# untitled.net
KiCad netlist of a schematic drawn in EAGLE
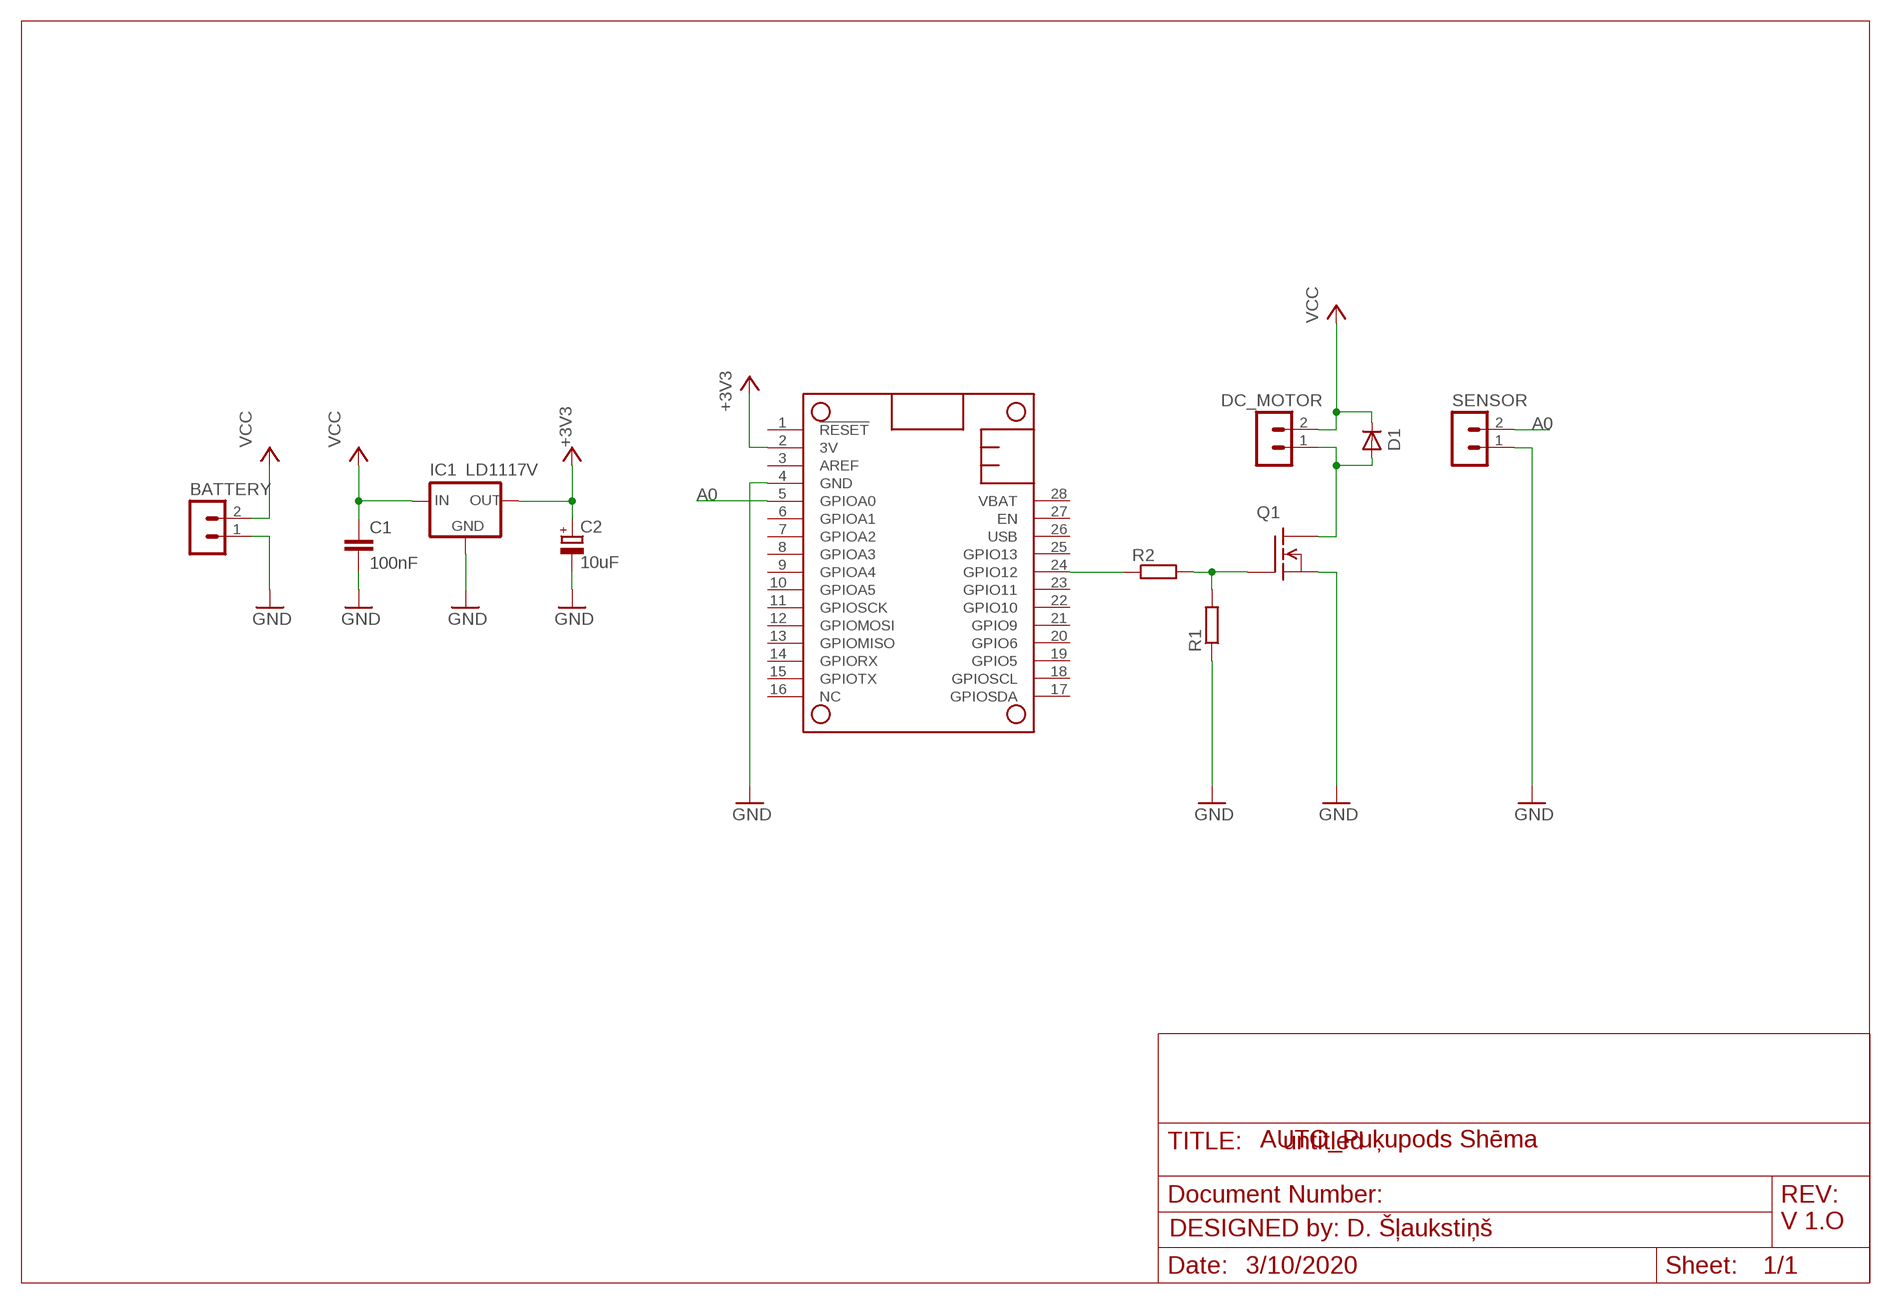
[diagram p0: schematic, sheet 1]

(export (version "E")
  (design (tool "Eeschema 10.0.6"))
  (components
    (comp (ref "BATTERY")
      (value "JST02_2.54")
      (footprint "eagle-import:JST02_2.54")
      (libsource (lib "eagle-import") (part "JST02_2.54"))
    )
    (comp (ref "C1")
      (value "100nF")
      (footprint "eagle-import:SMD_0603C")
      (libsource (lib "eagle-import") (part "CAP_CERAMIC_0603"))
    )
    (comp (ref "C2")
      (value "10uF")
      (footprint "eagle-import:E2,5-5")
      (libsource (lib "eagle-import") (part "CAP_POL_5MM"))
    )
    (comp (ref "D1")
      (value "1N4004")
      (footprint "eagle-import:DO41-10")
      (libsource (lib "eagle-import") (part "1N4004"))
    )
    (comp (ref "DC_MOTOR")
      (value "JST02_2.54")
      (footprint "eagle-import:JST02_2.54")
      (libsource (lib "eagle-import") (part "JST02_2.54"))
    )
    (comp (ref "IC1")
      (value "LD1117V")
      (footprint "eagle-import:78XXL")
      (libsource (lib "eagle-import") (part "V_REG_LD1117VXX"))
    )
    (comp (ref "MS1")
      (value "FEATHERWING")
      (footprint "eagle-import:FEATHERWING")
      (libsource (lib "eagle-import") (part "FEATHERWING"))
    )
    (comp (ref "Q1")
      (value "BSS97")
      (footprint "eagle-import:TO202")
      (libsource (lib "eagle-import") (part "BSS97"))
    )
    (comp (ref "R1")
      (value "RESISTOR_7.5MM_HORIZONTAL")
      (footprint "eagle-import:R-7.5MM")
      (libsource (lib "eagle-import") (part "RESISTOR_7.5MM_HORIZONTAL"))
    )
    (comp (ref "R2")
      (value "RESISTOR_7.5MM_HORIZONTAL")
      (footprint "eagle-import:R-7.5MM")
      (libsource (lib "eagle-import") (part "RESISTOR_7.5MM_HORIZONTAL"))
    )
    (comp (ref "SENSOR")
      (value "JST02_2.54")
      (footprint "eagle-import:JST02_2.54")
      (libsource (lib "eagle-import") (part "JST02_2.54"))
    )
  )
  (nets
    (net (code "1") (name "+3V3") (class "Default")
      (node (ref "C2") (pin "+") (pinfunction "+_+") (pintype "passive"))
      (node (ref "IC1") (pin "GND") (pinfunction "OUT_GND") (pintype "passive"))
      (node (ref "MS1") (pin "2") (pinfunction "3V_2") (pintype "power_in"))
    )
    (net (code "2") (name "/A0") (class "Default")
      (node (ref "MS1") (pin "5") (pinfunction "GPIOA0_5") (pintype "bidirectional"))
      (node (ref "SENSOR") (pin "2") (pinfunction "2_2") (pintype "passive"))
    )
    (net (code "3") (name "/USB") (class "Default")
      (node (ref "MS1") (pin "26") (pinfunction "USB_26") (pintype "power_in"))
    )
    (net (code "4") (name "/VBAT") (class "Default")
      (node (ref "MS1") (pin "28") (pinfunction "VBAT_28") (pintype "power_in"))
    )
    (net (code "5") (name "GND") (class "Default")
      (node (ref "BATTERY") (pin "1") (pinfunction "1_1") (pintype "passive"))
      (node (ref "C1") (pin "2") (pinfunction "2_2") (pintype "passive"))
      (node (ref "C2") (pin "-") (pinfunction "-_-") (pintype "passive"))
      (node (ref "IC1") (pin "IN") (pinfunction "GND_IN") (pintype "input"))
      (node (ref "MS1") (pin "4") (pinfunction "GND_4") (pintype "power_in"))
      (node (ref "Q1") (pin "1") (pinfunction "S_1") (pintype "passive"))
      (node (ref "R1") (pin "1") (pinfunction "1_1") (pintype "passive"))
      (node (ref "SENSOR") (pin "1") (pinfunction "1_1") (pintype "passive"))
    )
    (net (code "6") (name "Net-(MS1-GPIO12)") (class "Default")
      (node (ref "MS1") (pin "24") (pinfunction "GPIO12_24") (pintype "bidirectional"))
      (node (ref "R2") (pin "1") (pinfunction "1_1") (pintype "passive"))
    )
    (net (code "7") (name "Net-(Q1-D)") (class "Default")
      (node (ref "D1") (pin "A") (pinfunction "A_A") (pintype "passive"))
      (node (ref "DC_MOTOR") (pin "1") (pinfunction "1_1") (pintype "passive"))
      (node (ref "Q1") (pin "2") (pinfunction "D_2") (pintype "passive"))
    )
    (net (code "8") (name "Net-(Q1-G)") (class "Default")
      (node (ref "Q1") (pin "3") (pinfunction "G_3") (pintype "passive"))
      (node (ref "R1") (pin "2") (pinfunction "2_2") (pintype "passive"))
      (node (ref "R2") (pin "2") (pinfunction "2_2") (pintype "passive"))
    )
    (net (code "9") (name "VCC") (class "Default")
      (node (ref "BATTERY") (pin "2") (pinfunction "2_2") (pintype "passive"))
      (node (ref "C1") (pin "1") (pinfunction "1_1") (pintype "passive"))
      (node (ref "D1") (pin "C") (pinfunction "C_C") (pintype "passive"))
      (node (ref "DC_MOTOR") (pin "2") (pinfunction "2_2") (pintype "passive"))
      (node (ref "IC1") (pin "OUT") (pinfunction "IN_OUT") (pintype "input"))
    )
    (net (code "10") (name "unconnected-(MS1-AREF-Pad3)") (class "Default")
      (node (ref "MS1") (pin "3") (pinfunction "AREF_3") (pintype "passive"))
    )
    (net (code "11") (name "unconnected-(MS1-EN-Pad27)") (class "Default")
      (node (ref "MS1") (pin "27") (pinfunction "EN_27") (pintype "passive"))
    )
    (net (code "12") (name "unconnected-(MS1-GPIO5-Pad19)") (class "Default")
      (node (ref "MS1") (pin "19") (pinfunction "GPIO5_19") (pintype "bidirectional"))
    )
    (net (code "13") (name "unconnected-(MS1-GPIO6-Pad20)") (class "Default")
      (node (ref "MS1") (pin "20") (pinfunction "GPIO6_20") (pintype "bidirectional"))
    )
    (net (code "14") (name "unconnected-(MS1-GPIO9-Pad21)") (class "Default")
      (node (ref "MS1") (pin "21") (pinfunction "GPIO9_21") (pintype "bidirectional"))
    )
    (net (code "15") (name "unconnected-(MS1-GPIO10-Pad22)") (class "Default")
      (node (ref "MS1") (pin "22") (pinfunction "GPIO10_22") (pintype "bidirectional"))
    )
    (net (code "16") (name "unconnected-(MS1-GPIO11-Pad23)") (class "Default")
      (node (ref "MS1") (pin "23") (pinfunction "GPIO11_23") (pintype "bidirectional"))
    )
    (net (code "17") (name "unconnected-(MS1-GPIO13-Pad25)") (class "Default")
      (node (ref "MS1") (pin "25") (pinfunction "GPIO13_25") (pintype "bidirectional"))
    )
    (net (code "18") (name "unconnected-(MS1-GPIOA1-Pad6)") (class "Default")
      (node (ref "MS1") (pin "6") (pinfunction "GPIOA1_6") (pintype "bidirectional"))
    )
    (net (code "19") (name "unconnected-(MS1-GPIOA2-Pad7)") (class "Default")
      (node (ref "MS1") (pin "7") (pinfunction "GPIOA2_7") (pintype "bidirectional"))
    )
    (net (code "20") (name "unconnected-(MS1-GPIOA3-Pad8)") (class "Default")
      (node (ref "MS1") (pin "8") (pinfunction "GPIOA3_8") (pintype "bidirectional"))
    )
    (net (code "21") (name "unconnected-(MS1-GPIOA4-Pad9)") (class "Default")
      (node (ref "MS1") (pin "9") (pinfunction "GPIOA4_9") (pintype "bidirectional"))
    )
    (net (code "22") (name "unconnected-(MS1-GPIOA5-Pad10)") (class "Default")
      (node (ref "MS1") (pin "10") (pinfunction "GPIOA5_10") (pintype "bidirectional"))
    )
    (net (code "23") (name "unconnected-(MS1-GPIOMISO-Pad13)") (class "Default")
      (node (ref "MS1") (pin "13") (pinfunction "GPIOMISO_13") (pintype "bidirectional"))
    )
    (net (code "24") (name "unconnected-(MS1-GPIOMOSI-Pad12)") (class "Default")
      (node (ref "MS1") (pin "12") (pinfunction "GPIOMOSI_12") (pintype "bidirectional"))
    )
    (net (code "25") (name "unconnected-(MS1-GPIORX-Pad14)") (class "Default")
      (node (ref "MS1") (pin "14") (pinfunction "GPIORX_14") (pintype "bidirectional"))
    )
    (net (code "26") (name "unconnected-(MS1-GPIOSCK-Pad11)") (class "Default")
      (node (ref "MS1") (pin "11") (pinfunction "GPIOSCK_11") (pintype "bidirectional"))
    )
    (net (code "27") (name "unconnected-(MS1-GPIOSCL-Pad18)") (class "Default")
      (node (ref "MS1") (pin "18") (pinfunction "GPIOSCL_18") (pintype "bidirectional"))
    )
    (net (code "28") (name "unconnected-(MS1-GPIOSDA-Pad17)") (class "Default")
      (node (ref "MS1") (pin "17") (pinfunction "GPIOSDA_17") (pintype "bidirectional"))
    )
    (net (code "29") (name "unconnected-(MS1-GPIOTX-Pad15)") (class "Default")
      (node (ref "MS1") (pin "15") (pinfunction "GPIOTX_15") (pintype "bidirectional"))
    )
    (net (code "30") (name "unconnected-(MS1-NC-Pad16)") (class "Default")
      (node (ref "MS1") (pin "16") (pinfunction "NC_16") (pintype "passive"))
    )
    (net (code "31") (name "unconnected-(MS1-~{RESET}-Pad1)") (class "Default")
      (node (ref "MS1") (pin "1") (pinfunction "~{RESET}_1") (pintype "input"))
    )
  )
)
